# area-mon.net
KiCad netlist of a schematic drawn in EAGLE
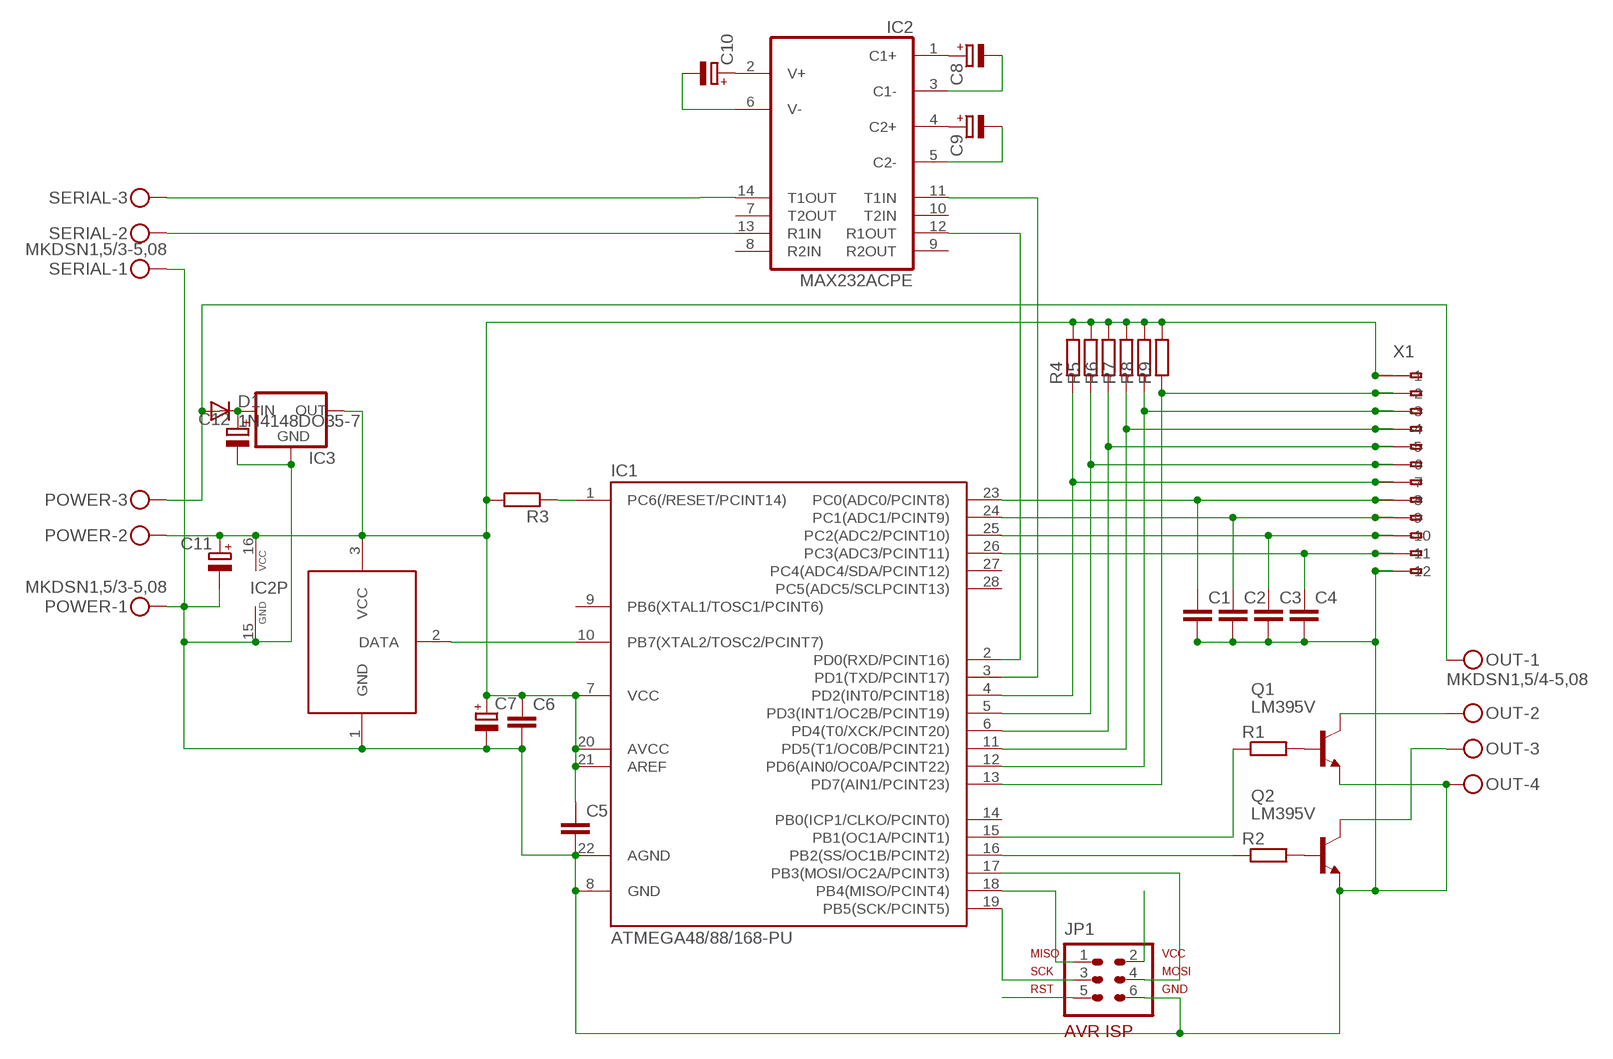
[diagram p0: schematic, sheet 1]

(export (version "E")
  (design (tool "Eeschema 10.0.6"))
  (components
    (comp (ref "C1")
      (value "C-EU050-024X044")
      (footprint "eagle-import:C050-024X044")
      (libsource (lib "eagle-import") (part "C-EU050-024X044"))
    )
    (comp (ref "C2")
      (value "C-EU050-024X044")
      (footprint "eagle-import:C050-024X044")
      (libsource (lib "eagle-import") (part "C-EU050-024X044"))
    )
    (comp (ref "C3")
      (value "C-EU050-024X044")
      (footprint "eagle-import:C050-024X044")
      (libsource (lib "eagle-import") (part "C-EU050-024X044"))
    )
    (comp (ref "C4")
      (value "C-EU050-024X044")
      (footprint "eagle-import:C050-024X044")
      (libsource (lib "eagle-import") (part "C-EU050-024X044"))
    )
    (comp (ref "C5")
      (value "C-EU050-024X044")
      (footprint "eagle-import:C050-024X044")
      (libsource (lib "eagle-import") (part "C-EU050-024X044"))
    )
    (comp (ref "C6")
      (value "C-EU050-024X044")
      (footprint "eagle-import:C050-024X044")
      (libsource (lib "eagle-import") (part "C-EU050-024X044"))
    )
    (comp (ref "C7")
      (value "CPOL-EUE5-8.5")
      (footprint "eagle-import:E5-8,5")
      (libsource (lib "eagle-import") (part "CPOL-EUE5-8.5"))
    )
    (comp (ref "C8")
      (value "CPOL-EUE2.5-5")
      (footprint "eagle-import:E2,5-5")
      (libsource (lib "eagle-import") (part "CPOL-EUE2.5-5"))
    )
    (comp (ref "C9")
      (value "CPOL-EUE2.5-5")
      (footprint "eagle-import:E2,5-5")
      (libsource (lib "eagle-import") (part "CPOL-EUE2.5-5"))
    )
    (comp (ref "C10")
      (value "CPOL-EUE2.5-5")
      (footprint "eagle-import:E2,5-5")
      (libsource (lib "eagle-import") (part "CPOL-EUE2.5-5"))
    )
    (comp (ref "C11")
      (value "CPOL-EUE2.5-5")
      (footprint "eagle-import:E2,5-5")
      (libsource (lib "eagle-import") (part "CPOL-EUE2.5-5"))
    )
    (comp (ref "C12")
      (value "CPOL-EUE2.5-5")
      (footprint "eagle-import:E2,5-5")
      (libsource (lib "eagle-import") (part "CPOL-EUE2.5-5"))
    )
    (comp (ref "D1")
      (value "1N4148DO35-7")
      (footprint "eagle-import:DO35-7")
      (libsource (lib "eagle-import") (part "1N4148DO35-7"))
    )
    (comp (ref "IC1")
      (value "ATMEGA48/88/168-PU")
      (footprint "eagle-import:DIL28-3")
      (libsource (lib "eagle-import") (part "ATMEGA48/88/168-PU"))
    )
    (comp (ref "IC2")
      (value "MAX232ACPE")
      (footprint "eagle-import:DIL16")
      (libsource (lib "eagle-import") (part "MAX232PEAC"))
    )
    (comp (ref "IC3")
      (value "78XXTO92L")
      (footprint "eagle-import:TO92L")
      (libsource (lib "eagle-import") (part "78XXTO92L"))
    )
    (comp (ref "JP1")
      (value "AVR-ISP-6VERT")
      (footprint "eagle-import:AVR-ISP-6")
      (libsource (lib "eagle-import") (part "AVR-ISP-6VERT"))
    )
    (comp (ref "OUT")
      (value "MKDSN1,5/4-5,08")
      (footprint "eagle-import:MKDSN1,5_4-5,08")
      (libsource (lib "eagle-import") (part "MKDSN1,5/4-5,08"))
    )
    (comp (ref "POWER")
      (value "MKDSN1,5/3-5,08")
      (footprint "eagle-import:MKDSN1,5_3-5,08")
      (libsource (lib "eagle-import") (part "MKDSN1,5/3-5,08"))
    )
    (comp (ref "Q1")
      (value "LM395V")
      (footprint "eagle-import:TO220V")
      (libsource (lib "eagle-import") (part "LM395V"))
    )
    (comp (ref "Q2")
      (value "LM395V")
      (footprint "eagle-import:TO220V")
      (libsource (lib "eagle-import") (part "LM395V"))
    )
    (comp (ref "R1")
      (value "R-EU0207/10")
      (footprint "eagle-import:0207_10")
      (libsource (lib "eagle-import") (part "R-EU0207/10"))
    )
    (comp (ref "R2")
      (value "R-EU0207/10")
      (footprint "eagle-import:0207_10")
      (libsource (lib "eagle-import") (part "R-EU0207/10"))
    )
    (comp (ref "R3")
      (value "R-EU0207/10")
      (footprint "eagle-import:0207_10")
      (libsource (lib "eagle-import") (part "R-EU0207/10"))
    )
    (comp (ref "R4")
      (value "R-EU0207/10")
      (footprint "eagle-import:0207_10")
      (libsource (lib "eagle-import") (part "R-EU0207/10"))
    )
    (comp (ref "R5")
      (value "R-EU0207/10")
      (footprint "eagle-import:0207_10")
      (libsource (lib "eagle-import") (part "R-EU0207/10"))
    )
    (comp (ref "R6")
      (value "R-EU0207/10")
      (footprint "eagle-import:0207_10")
      (libsource (lib "eagle-import") (part "R-EU0207/10"))
    )
    (comp (ref "R7")
      (value "R-EU0207/10")
      (footprint "eagle-import:0207_10")
      (libsource (lib "eagle-import") (part "R-EU0207/10"))
    )
    (comp (ref "R8")
      (value "R-EU0207/10")
      (footprint "eagle-import:0207_10")
      (libsource (lib "eagle-import") (part "R-EU0207/10"))
    )
    (comp (ref "R9")
      (value "R-EU0207/10")
      (footprint "eagle-import:0207_10")
      (libsource (lib "eagle-import") (part "R-EU0207/10"))
    )
    (comp (ref "SERIAL")
      (value "MKDSN1,5/3-5,08")
      (footprint "eagle-import:MKDSN1,5_3-5,08")
      (libsource (lib "eagle-import") (part "MKDSN1,5/3-5,08"))
    )
    (comp (ref "U$4")
      (value "DS18B20")
      (footprint "eagle-import:TO92-")
      (libsource (lib "eagle-import") (part "DS18B20"))
    )
    (comp (ref "X1")
      (value "233-512")
      (footprint "eagle-import:233-512")
      (fields
        (field (name "MF") "Wago Corporation")
        (field (name "MPN") "0233-0512")
        (field (name "MF_1") "Wago Corporation")
        (field (name "MPN_1") "0233-0512")
        (field (name "OC_FARNELL") "1777102")
        (field (name "OC_NEWARK") "79K2055")
      )
      (libsource (lib "eagle-import") (part "233-512"))
    )
  )
  (nets
    (net (code "1") (name "/RST") (class "Default")
      (node (ref "IC1") (pin "1") (pinfunction "PC6(/RESET/PCINT14)_1") (pintype "bidirectional"))
      (node (ref "JP1") (pin "5") (pinfunction "5_5") (pintype "passive"))
      (node (ref "R3") (pin "1") (pinfunction "1_1") (pintype "passive"))
    )
    (net (code "2") (name "/VCC") (class "Default")
      (node (ref "C11") (pin "+") (pinfunction "+_+") (pintype "passive"))
      (node (ref "C5") (pin "1") (pinfunction "1_1") (pintype "passive"))
      (node (ref "C6") (pin "1") (pinfunction "1_1") (pintype "passive"))
      (node (ref "C7") (pin "+") (pinfunction "+_+") (pintype "passive"))
      (node (ref "IC1") (pin "20") (pinfunction "AVCC_20") (pintype "passive"))
      (node (ref "IC1") (pin "21") (pinfunction "AREF_21") (pintype "passive"))
      (node (ref "IC1") (pin "7") (pinfunction "VCC_7") (pintype "power_in"))
      (node (ref "IC2") (pin "16") (pinfunction "VCC_16") (pintype "power_in"))
      (node (ref "IC3") (pin "3") (pinfunction "OUT_3") (pintype "passive"))
      (node (ref "JP1") (pin "2") (pinfunction "2_2") (pintype "passive"))
      (node (ref "POWER") (pin "2") (pinfunction "KL_2") (pintype "passive"))
      (node (ref "R3") (pin "2") (pinfunction "2_2") (pintype "passive"))
      (node (ref "R4") (pin "2") (pinfunction "2_2") (pintype "passive"))
      (node (ref "R5") (pin "2") (pinfunction "2_2") (pintype "passive"))
      (node (ref "R6") (pin "2") (pinfunction "2_2") (pintype "passive"))
      (node (ref "R7") (pin "2") (pinfunction "2_2") (pintype "passive"))
      (node (ref "R8") (pin "2") (pinfunction "2_2") (pintype "passive"))
      (node (ref "R9") (pin "2") (pinfunction "2_2") (pintype "passive"))
      (node (ref "U$4") (pin "3") (pinfunction "VCC_3") (pintype "power_in"))
      (node (ref "X1") (pin "A1") (pinfunction "-1_A1") (pintype "passive"))
      (node (ref "X1") (pin "B1") (pinfunction "B-1_B1") (pintype "passive"))
    )
    (net (code "3") (name "Net-(IC1-AGND)") (class "Default")
      (node (ref "C1") (pin "2") (pinfunction "2_2") (pintype "passive"))
      (node (ref "C11") (pin "-") (pinfunction "-_-") (pintype "passive"))
      (node (ref "C12") (pin "-") (pinfunction "-_-") (pintype "passive"))
      (node (ref "C2") (pin "2") (pinfunction "2_2") (pintype "passive"))
      (node (ref "C3") (pin "2") (pinfunction "2_2") (pintype "passive"))
      (node (ref "C4") (pin "2") (pinfunction "2_2") (pintype "passive"))
      (node (ref "C5") (pin "2") (pinfunction "2_2") (pintype "passive"))
      (node (ref "C6") (pin "2") (pinfunction "2_2") (pintype "passive"))
      (node (ref "C7") (pin "-") (pinfunction "-_-") (pintype "passive"))
      (node (ref "IC1") (pin "22") (pinfunction "AGND_22") (pintype "power_in"))
      (node (ref "IC1") (pin "8") (pinfunction "GND_8") (pintype "power_in"))
      (node (ref "IC2") (pin "15") (pinfunction "GND_15") (pintype "power_in"))
      (node (ref "IC3") (pin "2") (pinfunction "GND_2") (pintype "input"))
      (node (ref "JP1") (pin "6") (pinfunction "6_6") (pintype "passive"))
      (node (ref "OUT") (pin "4") (pinfunction "KL_4") (pintype "passive"))
      (node (ref "POWER") (pin "1") (pinfunction "KL_1") (pintype "passive"))
      (node (ref "Q1") (pin "C") (pinfunction "E_C") (pintype "passive"))
      (node (ref "Q2") (pin "C") (pinfunction "E_C") (pintype "passive"))
      (node (ref "SERIAL") (pin "1") (pinfunction "KL_1") (pintype "passive"))
      (node (ref "U$4") (pin "1") (pinfunction "GND_1") (pintype "power_in"))
      (node (ref "X1") (pin "A12") (pinfunction "-12_A12") (pintype "passive"))
      (node (ref "X1") (pin "B12") (pinfunction "B-12_B12") (pintype "passive"))
    )
    (net (code "4") (name "Net-(IC1-PB1(OC1A{slash}PCINT1))") (class "Default")
      (node (ref "IC1") (pin "15") (pinfunction "PB1(OC1A/PCINT1)_15") (pintype "bidirectional"))
      (node (ref "R1") (pin "1") (pinfunction "1_1") (pintype "passive"))
    )
    (net (code "5") (name "Net-(IC1-PB2(SS{slash}OC1B{slash}PCINT2))") (class "Default")
      (node (ref "IC1") (pin "16") (pinfunction "PB2(SS/OC1B/PCINT2)_16") (pintype "bidirectional"))
      (node (ref "R2") (pin "1") (pinfunction "1_1") (pintype "passive"))
    )
    (net (code "6") (name "Net-(IC1-PB3(MOSI{slash}OC2A{slash}PCINT3))") (class "Default")
      (node (ref "IC1") (pin "17") (pinfunction "PB3(MOSI/OC2A/PCINT3)_17") (pintype "bidirectional"))
      (node (ref "JP1") (pin "4") (pinfunction "4_4") (pintype "passive"))
    )
    (net (code "7") (name "Net-(IC1-PB4(MISO{slash}PCINT4))") (class "Default")
      (node (ref "IC1") (pin "18") (pinfunction "PB4(MISO/PCINT4)_18") (pintype "bidirectional"))
      (node (ref "JP1") (pin "1") (pinfunction "1_1") (pintype "passive"))
    )
    (net (code "8") (name "Net-(IC1-PB5(SCK{slash}PCINT5))") (class "Default")
      (node (ref "IC1") (pin "19") (pinfunction "PB5(SCK/PCINT5)_19") (pintype "bidirectional"))
      (node (ref "JP1") (pin "3") (pinfunction "3_3") (pintype "passive"))
    )
    (net (code "9") (name "Net-(IC1-PB7(XTAL2{slash}TOSC2{slash}PCINT7))") (class "Default")
      (node (ref "IC1") (pin "10") (pinfunction "PB7(XTAL2/TOSC2/PCINT7)_10") (pintype "bidirectional"))
      (node (ref "U$4") (pin "2") (pinfunction "DATA_2") (pintype "output"))
    )
    (net (code "10") (name "Net-(IC1-PC0(ADC0{slash}PCINT8))") (class "Default")
      (node (ref "C1") (pin "1") (pinfunction "1_1") (pintype "passive"))
      (node (ref "IC1") (pin "23") (pinfunction "PC0(ADC0/PCINT8)_23") (pintype "bidirectional"))
      (node (ref "X1") (pin "A8") (pinfunction "-8_A8") (pintype "passive"))
      (node (ref "X1") (pin "B8") (pinfunction "B-8_B8") (pintype "passive"))
    )
    (net (code "11") (name "Net-(IC1-PC1(ADC1{slash}PCINT9))") (class "Default")
      (node (ref "C2") (pin "1") (pinfunction "1_1") (pintype "passive"))
      (node (ref "IC1") (pin "24") (pinfunction "PC1(ADC1/PCINT9)_24") (pintype "bidirectional"))
      (node (ref "X1") (pin "A9") (pinfunction "-9_A9") (pintype "passive"))
      (node (ref "X1") (pin "B9") (pinfunction "B-9_B9") (pintype "passive"))
    )
    (net (code "12") (name "Net-(IC1-PC2(ADC2{slash}PCINT10))") (class "Default")
      (node (ref "C3") (pin "1") (pinfunction "1_1") (pintype "passive"))
      (node (ref "IC1") (pin "25") (pinfunction "PC2(ADC2/PCINT10)_25") (pintype "bidirectional"))
      (node (ref "X1") (pin "A10") (pinfunction "-10_A10") (pintype "passive"))
      (node (ref "X1") (pin "B10") (pinfunction "B-10_B10") (pintype "passive"))
    )
    (net (code "13") (name "Net-(IC1-PC3(ADC3{slash}PCINT11))") (class "Default")
      (node (ref "C4") (pin "1") (pinfunction "1_1") (pintype "passive"))
      (node (ref "IC1") (pin "26") (pinfunction "PC3(ADC3/PCINT11)_26") (pintype "bidirectional"))
      (node (ref "X1") (pin "A11") (pinfunction "-11_A11") (pintype "passive"))
      (node (ref "X1") (pin "B11") (pinfunction "B-11_B11") (pintype "passive"))
    )
    (net (code "14") (name "Net-(IC1-PD0(RXD{slash}PCINT16))") (class "Default")
      (node (ref "IC1") (pin "2") (pinfunction "PD0(RXD/PCINT16)_2") (pintype "bidirectional"))
      (node (ref "IC2") (pin "12") (pinfunction "R1OUT_12") (pintype "output"))
    )
    (net (code "15") (name "Net-(IC1-PD1(TXD{slash}PCINT17))") (class "Default")
      (node (ref "IC1") (pin "3") (pinfunction "PD1(TXD/PCINT17)_3") (pintype "bidirectional"))
      (node (ref "IC2") (pin "11") (pinfunction "T1IN_11") (pintype "input"))
    )
    (net (code "16") (name "Net-(IC1-PD2(INT0{slash}PCINT18))") (class "Default")
      (node (ref "IC1") (pin "4") (pinfunction "PD2(INT0/PCINT18)_4") (pintype "bidirectional"))
      (node (ref "R4") (pin "1") (pinfunction "1_1") (pintype "passive"))
      (node (ref "X1") (pin "A7") (pinfunction "-7_A7") (pintype "passive"))
      (node (ref "X1") (pin "B7") (pinfunction "B-7_B7") (pintype "passive"))
    )
    (net (code "17") (name "Net-(IC1-PD3(INT1{slash}OC2B{slash}PCINT19))") (class "Default")
      (node (ref "IC1") (pin "5") (pinfunction "PD3(INT1/OC2B/PCINT19)_5") (pintype "bidirectional"))
      (node (ref "R5") (pin "1") (pinfunction "1_1") (pintype "passive"))
      (node (ref "X1") (pin "A6") (pinfunction "-6_A6") (pintype "passive"))
      (node (ref "X1") (pin "B6") (pinfunction "B-6_B6") (pintype "passive"))
    )
    (net (code "18") (name "Net-(IC1-PD4(T0{slash}XCK{slash}PCINT20))") (class "Default")
      (node (ref "IC1") (pin "6") (pinfunction "PD4(T0/XCK/PCINT20)_6") (pintype "bidirectional"))
      (node (ref "R6") (pin "1") (pinfunction "1_1") (pintype "passive"))
      (node (ref "X1") (pin "A5") (pinfunction "-5_A5") (pintype "passive"))
      (node (ref "X1") (pin "B5") (pinfunction "B-5_B5") (pintype "passive"))
    )
    (net (code "19") (name "Net-(IC1-PD5(T1{slash}OC0B{slash}PCINT21))") (class "Default")
      (node (ref "IC1") (pin "11") (pinfunction "PD5(T1/OC0B/PCINT21)_11") (pintype "bidirectional"))
      (node (ref "R7") (pin "1") (pinfunction "1_1") (pintype "passive"))
      (node (ref "X1") (pin "A4") (pinfunction "-4_A4") (pintype "passive"))
      (node (ref "X1") (pin "B4") (pinfunction "B-4_B4") (pintype "passive"))
    )
    (net (code "20") (name "Net-(IC1-PD6(AIN0{slash}OC0A{slash}PCINT22))") (class "Default")
      (node (ref "IC1") (pin "12") (pinfunction "PD6(AIN0/OC0A/PCINT22)_12") (pintype "bidirectional"))
      (node (ref "R8") (pin "1") (pinfunction "1_1") (pintype "passive"))
      (node (ref "X1") (pin "A3") (pinfunction "-3_A3") (pintype "passive"))
      (node (ref "X1") (pin "B3") (pinfunction "B-3_B3") (pintype "passive"))
    )
    (net (code "21") (name "Net-(IC1-PD7(AIN1{slash}PCINT23))") (class "Default")
      (node (ref "IC1") (pin "13") (pinfunction "PD7(AIN1/PCINT23)_13") (pintype "bidirectional"))
      (node (ref "R9") (pin "1") (pinfunction "1_1") (pintype "passive"))
      (node (ref "X1") (pin "A2") (pinfunction "-2_A2") (pintype "passive"))
      (node (ref "X1") (pin "B2") (pinfunction "B-2_B2") (pintype "passive"))
    )
    (net (code "22") (name "Net-(IC2A-C1+)") (class "Default")
      (node (ref "C8") (pin "+") (pinfunction "+_+") (pintype "passive"))
      (node (ref "IC2") (pin "1") (pinfunction "C1+_1") (pintype "bidirectional"))
    )
    (net (code "23") (name "Net-(IC2A-C1-)") (class "Default")
      (node (ref "C8") (pin "-") (pinfunction "-_-") (pintype "passive"))
      (node (ref "IC2") (pin "3") (pinfunction "C1-_3") (pintype "bidirectional"))
    )
    (net (code "24") (name "Net-(IC2A-C2+)") (class "Default")
      (node (ref "C9") (pin "+") (pinfunction "+_+") (pintype "passive"))
      (node (ref "IC2") (pin "4") (pinfunction "C2+_4") (pintype "bidirectional"))
    )
    (net (code "25") (name "Net-(IC2A-C2-)") (class "Default")
      (node (ref "C9") (pin "-") (pinfunction "-_-") (pintype "passive"))
      (node (ref "IC2") (pin "5") (pinfunction "C2-_5") (pintype "bidirectional"))
    )
    (net (code "26") (name "Net-(IC2A-R1IN)") (class "Default")
      (node (ref "IC2") (pin "13") (pinfunction "R1IN_13") (pintype "input"))
      (node (ref "SERIAL") (pin "2") (pinfunction "KL_2") (pintype "passive"))
    )
    (net (code "27") (name "Net-(IC2A-T1OUT)") (class "Default")
      (node (ref "IC2") (pin "14") (pinfunction "T1OUT_14") (pintype "output"))
      (node (ref "SERIAL") (pin "3") (pinfunction "KL_3") (pintype "passive"))
    )
    (net (code "28") (name "Net-(IC2A-V+)") (class "Default")
      (node (ref "C10") (pin "+") (pinfunction "+_+") (pintype "passive"))
      (node (ref "IC2") (pin "2") (pinfunction "V+_2") (pintype "bidirectional"))
    )
    (net (code "29") (name "Net-(IC2A-V-)") (class "Default")
      (node (ref "C10") (pin "-") (pinfunction "-_-") (pintype "passive"))
      (node (ref "IC2") (pin "6") (pinfunction "V-_6") (pintype "bidirectional"))
    )
    (net (code "30") (name "Net-(IC3-IN)") (class "Default")
      (node (ref "C12") (pin "+") (pinfunction "+_+") (pintype "passive"))
      (node (ref "D1") (pin "C") (pinfunction "C_C") (pintype "passive"))
      (node (ref "IC3") (pin "1") (pinfunction "IN_1") (pintype "input"))
    )
    (net (code "31") (name "Net-(OUTA-KL)") (class "Default")
      (node (ref "D1") (pin "A") (pinfunction "A_A") (pintype "passive"))
      (node (ref "OUT") (pin "1") (pinfunction "KL_1") (pintype "passive"))
      (node (ref "POWER") (pin "3") (pinfunction "KL_3") (pintype "passive"))
    )
    (net (code "32") (name "Net-(OUTB-KL)") (class "Default")
      (node (ref "OUT") (pin "2") (pinfunction "KL_2") (pintype "passive"))
      (node (ref "Q1") (pin "E") (pinfunction "C_E") (pintype "passive"))
    )
    (net (code "33") (name "Net-(OUTC-KL)") (class "Default")
      (node (ref "OUT") (pin "3") (pinfunction "KL_3") (pintype "passive"))
      (node (ref "Q2") (pin "E") (pinfunction "C_E") (pintype "passive"))
    )
    (net (code "34") (name "Net-(Q1-PadB)") (class "Default")
      (node (ref "Q1") (pin "B") (pinfunction "B_B") (pintype "passive"))
      (node (ref "R1") (pin "2") (pinfunction "2_2") (pintype "passive"))
    )
    (net (code "35") (name "Net-(Q2-PadB)") (class "Default")
      (node (ref "Q2") (pin "B") (pinfunction "B_B") (pintype "passive"))
      (node (ref "R2") (pin "2") (pinfunction "2_2") (pintype "passive"))
    )
    (net (code "36") (name "unconnected-(IC1-PB0(ICP1{slash}CLKO{slash}PCINT0)-Pad14)") (class "Default")
      (node (ref "IC1") (pin "14") (pinfunction "PB0(ICP1/CLKO/PCINT0)_14") (pintype "bidirectional"))
    )
    (net (code "37") (name "unconnected-(IC1-PB6(XTAL1{slash}TOSC1{slash}PCINT6)-Pad9)") (class "Default")
      (node (ref "IC1") (pin "9") (pinfunction "PB6(XTAL1/TOSC1/PCINT6)_9") (pintype "bidirectional"))
    )
    (net (code "38") (name "unconnected-(IC1-PC4(ADC4{slash}SDA{slash}PCINT12)-Pad27)") (class "Default")
      (node (ref "IC1") (pin "27") (pinfunction "PC4(ADC4/SDA/PCINT12)_27") (pintype "bidirectional"))
    )
    (net (code "39") (name "unconnected-(IC1-PC5(ADC5{slash}SCLPCINT13)-Pad28)") (class "Default")
      (node (ref "IC1") (pin "28") (pinfunction "PC5(ADC5/SCLPCINT13)_28") (pintype "bidirectional"))
    )
    (net (code "40") (name "unconnected-(IC2A-R2IN-Pad8)") (class "Default")
      (node (ref "IC2") (pin "8") (pinfunction "R2IN_8") (pintype "input"))
    )
    (net (code "41") (name "unconnected-(IC2A-R2OUT-Pad9)") (class "Default")
      (node (ref "IC2") (pin "9") (pinfunction "R2OUT_9") (pintype "output"))
    )
    (net (code "42") (name "unconnected-(IC2A-T2IN-Pad10)") (class "Default")
      (node (ref "IC2") (pin "10") (pinfunction "T2IN_10") (pintype "input"))
    )
    (net (code "43") (name "unconnected-(IC2A-T2OUT-Pad7)") (class "Default")
      (node (ref "IC2") (pin "7") (pinfunction "T2OUT_7") (pintype "output"))
    )
  )
)
